# light.net
KiCad netlist of a schematic drawn in Altium Designer
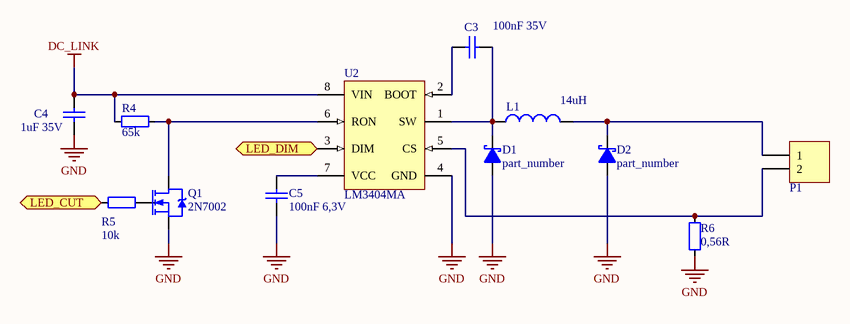
[diagram p0: light.SchDoc]

(export (version "E")
  (design (tool "Eeschema 10.0.6"))
  (components
    (comp (ref "C3")
      (value "100nF 35V")
      (footprint "0603_CAP")
      (description "Ceramic capacitor")
      (libsource (lib "Library_Altium_KNR") (part "Cap"))
    )
    (comp (ref "C4")
      (value "1uF 35V")
      (footprint "0603_CAP")
      (description "Ceramic capacitor")
      (libsource (lib "Library_Altium_KNR") (part "Cap"))
    )
    (comp (ref "C5")
      (value "100nF 6,3V")
      (footprint "0603_CAP")
      (description "Ceramic capacitor")
      (libsource (lib "Library_Altium_KNR") (part "Cap"))
    )
    (comp (ref "D1")
      (value "part_number")
      (footprint "DO-219AB (SMF)")
      (description "schottky")
      (libsource (lib "Diodes") (part "Schottky"))
    )
    (comp (ref "D2")
      (value "part_number")
      (footprint "DO-219AB (SMF)")
      (description "schottky")
      (libsource (lib "Diodes") (part "Schottky"))
    )
    (comp (ref "L1")
      (value "14uH")
      (footprint "Inductors:PA4341.223ANLT")
      (libsource (lib "my_lib_ext") (part "Inductor"))
    )
    (comp (ref "P1")
      (value "HDR1X2")
      (footprint "HDR1X2")
      (description "Header, 2-Pin")
      (fields (field (name "PUBLISHER") "Altium Limited"))
      (libsource (lib "KNR_Kurs") (part "HDR1X2"))
    )
    (comp (ref "Q1")
      (value "2N7002")
      (footprint "Transistors:Sot23")
      (libsource (lib "KNR_Kurs_K") (part "2N7002"))
    )
    (comp (ref "R4")
      (value "65k")
      (footprint "0603")
      (description "Resistior")
      (libsource (lib "") (part "RES_1"))
    )
    (comp (ref "R5")
      (value "10k")
      (footprint "0603")
      (description "Resistior")
      (libsource (lib "") (part "RES_1"))
    )
    (comp (ref "R6")
      (value "0,56R")
      (footprint "1206")
      (description "Resistior")
      (libsource (lib "Library_Altium_KNR") (part "RES"))
    )
    (comp (ref "U2")
      (value "LM3404MA")
      (footprint "M08A_N")
      (description "1.0A Constant Current Buck Regulator for High Power LED Drivers, 8-pin Narrow SOIC")
      (fields
        (field (name "MANUFACTURER") "National Semiconductor")
        (field (name "HELPURL") "C:\\Users\\micha\\Documents\\Studia\\Inżynierka\\Elektronika\\Datasheets\\LM3404.pdf")
      )
      (libsource (lib "National Semiconductor MiscPower") (part "LM3404MA"))
    )
  )
  (nets
    (net (code "1") (name "/LED_CUT") (class "Default")
      (node (ref "R5") (pin "1") (pinfunction "1_1") (pintype "passive"))
    )
    (net (code "2") (name "/LED_DIM") (class "Default")
      (node (ref "U2") (pin "3") (pinfunction "DIM_3") (pintype "input"))
    )
    (net (code "3") (name "DC_LINK") (class "Default")
      (node (ref "C4") (pin "2") (pinfunction "2_2") (pintype "passive"))
      (node (ref "R4") (pin "1") (pinfunction "1_1") (pintype "passive"))
      (node (ref "U2") (pin "8") (pinfunction "VIN_8") (pintype "power_in"))
    )
    (net (code "4") (name "GND") (class "Default")
      (node (ref "C4") (pin "1") (pinfunction "1_1") (pintype "passive"))
      (node (ref "C5") (pin "1") (pinfunction "1_1") (pintype "passive"))
      (node (ref "D1") (pin "1") (pinfunction "A_1") (pintype "passive"))
      (node (ref "D2") (pin "1") (pinfunction "A_1") (pintype "passive"))
      (node (ref "Q1") (pin "3") (pinfunction "S_3") (pintype "passive"))
      (node (ref "R6") (pin "1") (pinfunction "1_1") (pintype "passive"))
      (node (ref "U2") (pin "4") (pinfunction "GND_4") (pintype "power_in"))
    )
    (net (code "5") (name "Net-(D1-K)") (class "Default")
      (node (ref "C3") (pin "1") (pinfunction "1_1") (pintype "passive"))
      (node (ref "D1") (pin "2") (pinfunction "K_2") (pintype "passive"))
      (node (ref "L1") (pin "1") (pinfunction "1_1") (pintype "passive"))
      (node (ref "U2") (pin "1") (pinfunction "SW_1") (pintype "power_in"))
    )
    (net (code "6") (name "Net-(D2-K)") (class "Default")
      (node (ref "D2") (pin "2") (pinfunction "K_2") (pintype "passive"))
      (node (ref "L1") (pin "2") (pinfunction "0_2") (pintype "passive"))
      (node (ref "P1") (pin "1") (pinfunction "1_1") (pintype "passive"))
    )
    (net (code "7") (name "Net-(Q1-D)") (class "Default")
      (node (ref "Q1") (pin "2") (pinfunction "D_2") (pintype "passive"))
      (node (ref "R4") (pin "2") (pinfunction "2_2") (pintype "passive"))
      (node (ref "U2") (pin "6") (pinfunction "RON_6") (pintype "input"))
    )
    (net (code "8") (name "Net-(Q1-G)") (class "Default")
      (node (ref "Q1") (pin "1") (pinfunction "G_1") (pintype "passive"))
      (node (ref "R5") (pin "2") (pinfunction "2_2") (pintype "passive"))
    )
    (net (code "9") (name "Net-(U2-BOOT)") (class "Default")
      (node (ref "C3") (pin "2") (pinfunction "2_2") (pintype "passive"))
      (node (ref "U2") (pin "2") (pinfunction "BOOT_2") (pintype "input"))
    )
    (net (code "10") (name "Net-(U2-CS)") (class "Default")
      (node (ref "P1") (pin "2") (pinfunction "2_2") (pintype "passive"))
      (node (ref "R6") (pin "2") (pinfunction "2_2") (pintype "passive"))
      (node (ref "U2") (pin "5") (pinfunction "CS_5") (pintype "input"))
    )
    (net (code "11") (name "Net-(U2-VCC)") (class "Default")
      (node (ref "C5") (pin "2") (pinfunction "2_2") (pintype "passive"))
      (node (ref "U2") (pin "7") (pinfunction "VCC_7") (pintype "power_in"))
    )
  )
)
